# 03_METER_PWM_KEY.net
KiCad netlist of a schematic drawn in Altium Designer
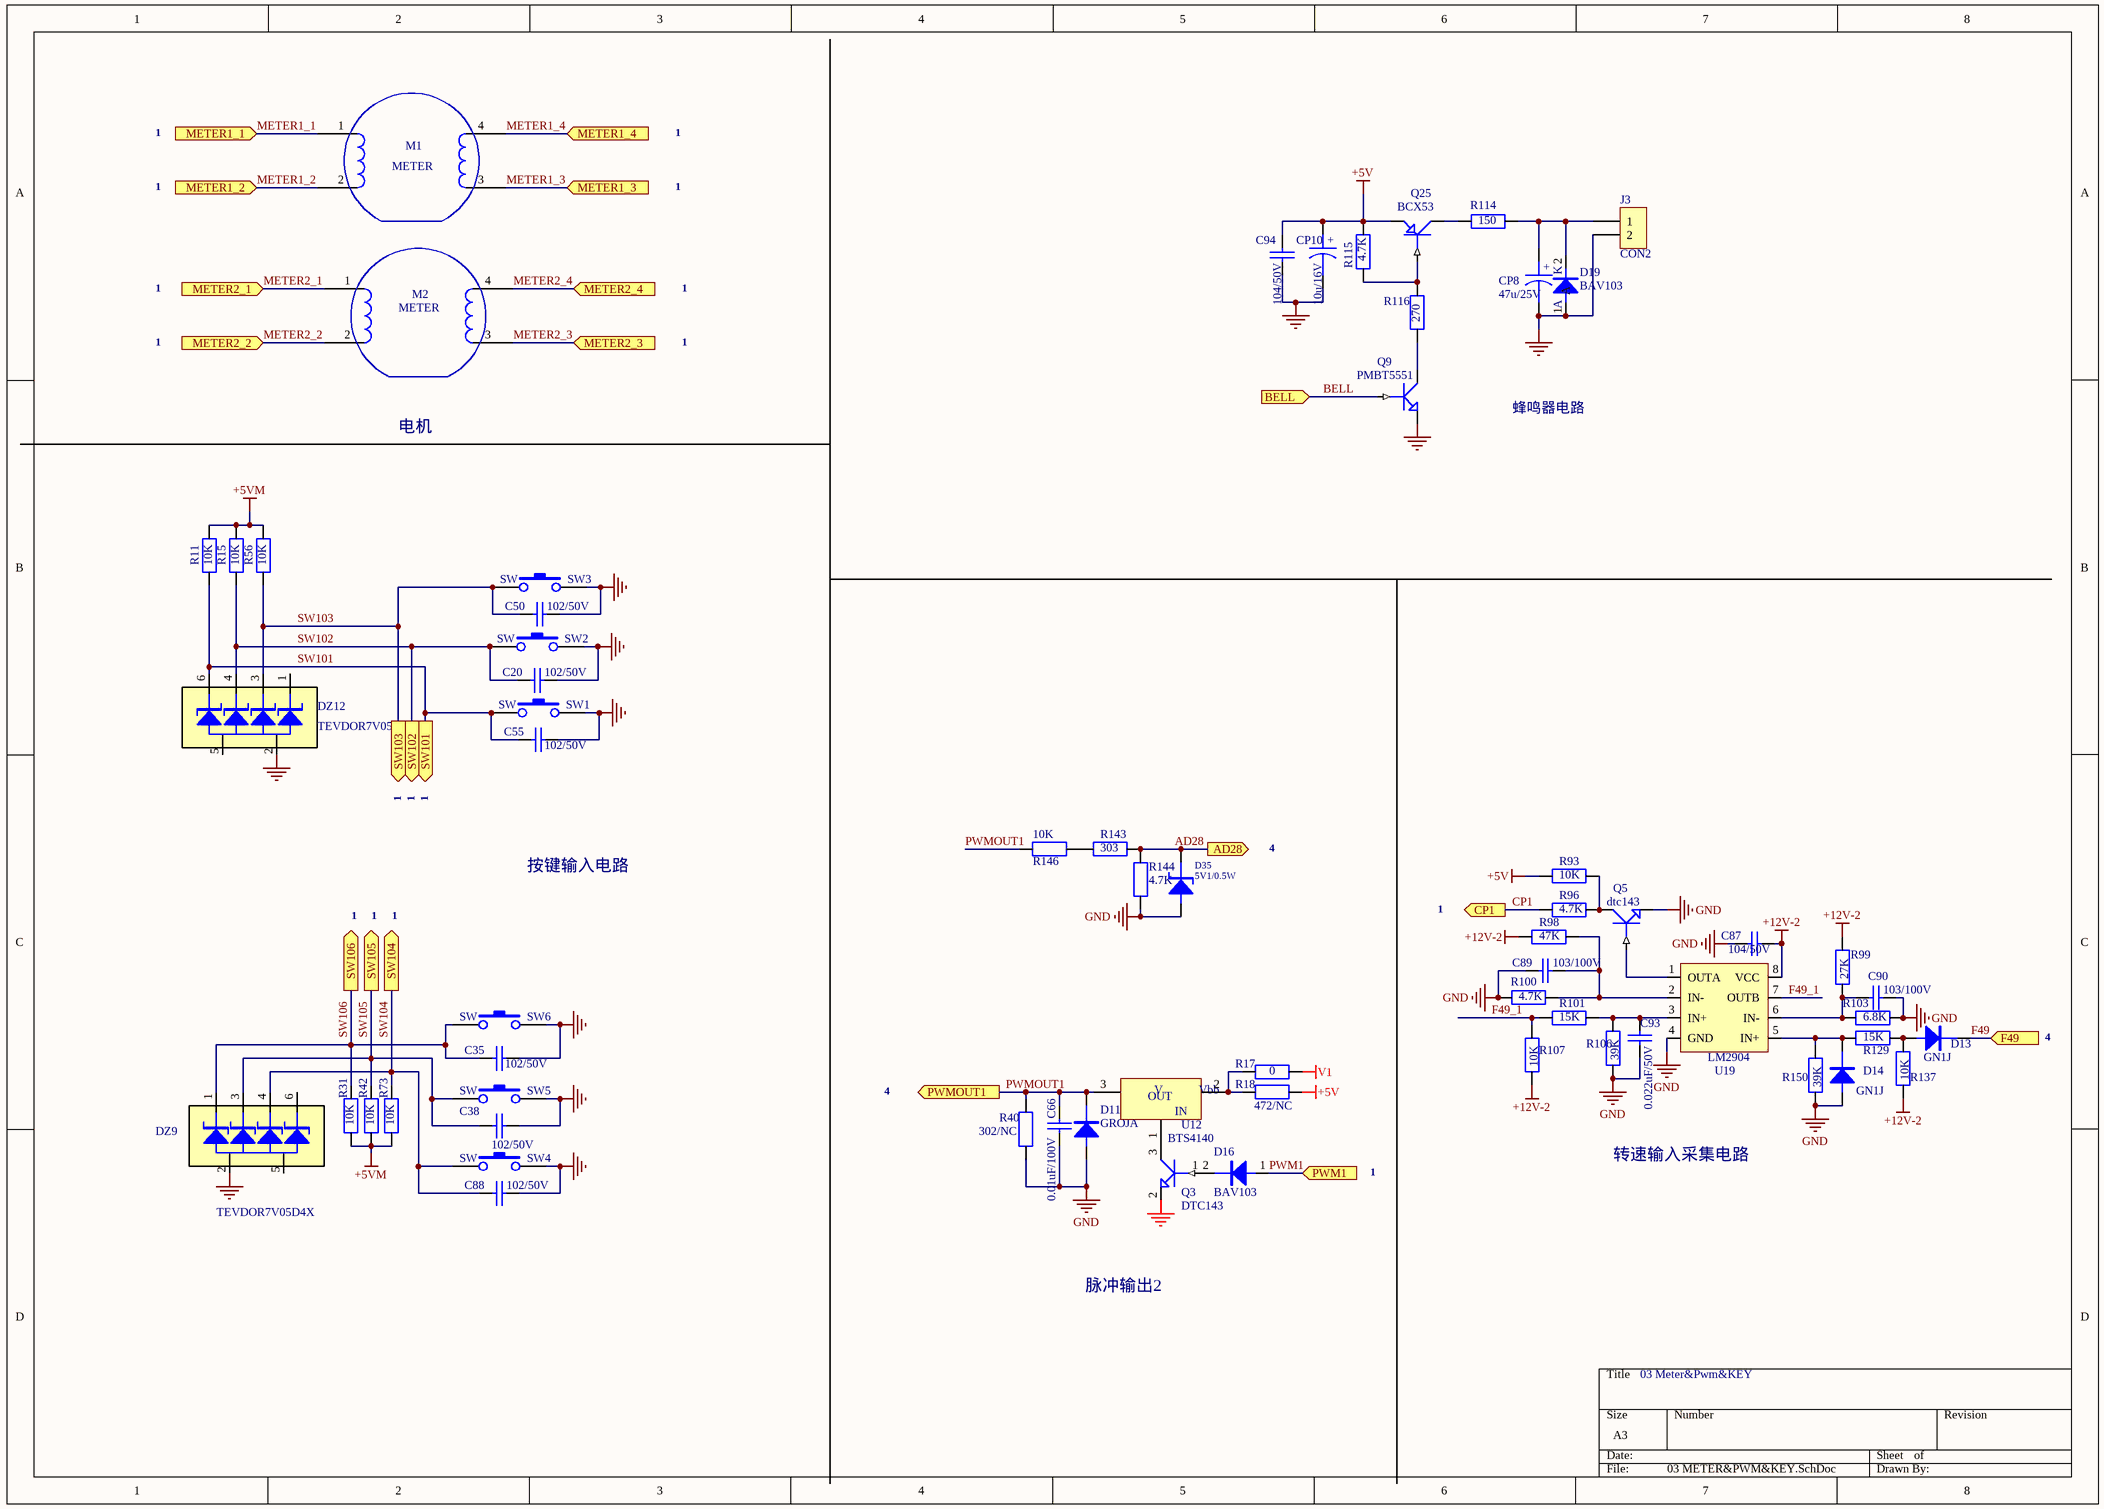
[diagram p0: 03 METER&PWM&KEY.SchDoc]

(export (version "E")
  (design (tool "Eeschema 10.0.6"))
  (components
    (comp (ref "C20")
      (value "102/50V")
      (footprint "CR0805")
      (description "Capacitor")
      (libsource (lib "*") (part "CAP"))
    )
    (comp (ref "C35")
      (value "102/50V")
      (footprint "CR0805")
      (description "Capacitor")
      (libsource (lib "*") (part "CAP"))
    )
    (comp (ref "C38")
      (value "102/50V")
      (footprint "CR0805")
      (description "Capacitor")
      (libsource (lib "*") (part "CAP"))
    )
    (comp (ref "C50")
      (value "102/50V")
      (footprint "CR0805")
      (description "Capacitor")
      (libsource (lib "*") (part "CAP"))
    )
    (comp (ref "C55")
      (value "102/50V")
      (footprint "CR0805")
      (description "Capacitor")
      (libsource (lib "*") (part "CAP"))
    )
    (comp (ref "C66")
      (value "0.01uF/100V")
      (footprint "CR0805")
      (description "Capacitor")
      (libsource (lib "*") (part "CAP"))
    )
    (comp (ref "C87")
      (value "104/50V")
      (footprint "CR0805")
      (description "贴片电容")
      (libsource (lib "HNS-SCH") (part "CAP"))
    )
    (comp (ref "C88")
      (value "102/50V")
      (footprint "CR0805")
      (description "Capacitor")
      (libsource (lib "*") (part "CAP"))
    )
    (comp (ref "C89")
      (value "103/100V")
      (footprint "CR0805")
      (description "贴片电容")
      (libsource (lib "HNS-SCH") (part "CAP"))
    )
    (comp (ref "C90")
      (value "103/100V")
      (footprint "CR0805")
      (description "贴片电容")
      (libsource (lib "HNS-SCH") (part "CAP"))
    )
    (comp (ref "C93")
      (value "0.022uF/50V")
      (footprint "CR0805")
      (description "Capacitor")
      (libsource (lib "*") (part "CAP"))
    )
    (comp (ref "C94")
      (value "104/50V")
      (footprint "CR0805")
      (description "贴片电容")
      (libsource (lib "YDM-SQ-1SCH") (part "CAP"))
    )
    (comp (ref "CP8")
      (value "47u/25V")
      (footprint "10uF/25V")
      (description "Capacitor")
      (libsource (lib "*") (part "CAPACITOR POL"))
    )
    (comp (ref "CP10")
      (value "10u/16V")
      (footprint "CE1206")
      (description "Capacitor")
      (libsource (lib "*") (part "CAPACITOR POL"))
    )
    (comp (ref "D11")
      (value "GROJA")
      (footprint "SMA")
      (description "二极管")
      (libsource (lib "*") (part "DIODE"))
    )
    (comp (ref "D13")
      (value "GN1J")
      (footprint "SMA")
      (description "二极管")
      (libsource (lib "*") (part "DIODE"))
    )
    (comp (ref "D14")
      (value "GN1J")
      (footprint "SMA")
      (description "二极管")
      (libsource (lib "*") (part "DIODE"))
    )
    (comp (ref "D16")
      (value "BAV103")
      (footprint "SOD-80C")
      (description "二极管")
      (libsource (lib "") (part "DIODE_1"))
    )
    (comp (ref "D19")
      (value "BAV103")
      (footprint "SOD-80C")
      (description "二极管")
      (libsource (lib "HNS-SCH") (part "GN1J"))
    )
    (comp (ref "D35")
      (value "5V1/0.5W")
      (footprint "SOD-80C")
      (description "稳压二极管")
      (libsource (lib "*") (part "DW"))
    )
    (comp (ref "DZ9")
      (value "TEVDOR7V05D4X")
      (footprint "SOT-457")
      (description "二极管排")
      (libsource (lib "*") (part "TEVDOR7V05D4X"))
    )
    (comp (ref "DZ12")
      (value "TEVDOR7V05D4X")
      (footprint "SOT-457")
      (description "二极管排")
      (libsource (lib "") (part "TEVDOR7V05D4X_1"))
    )
    (comp (ref "J3")
      (value "CON2")
      (footprint "DIP 1X2 2.5mm")
      (description "连接器-2PIN")
      (libsource (lib "HNS-SCH") (part "CON2"))
    )
    (comp (ref "M1") (value "METER") (footprint "METER2") (libsource (lib "*") (part "METER")))
    (comp (ref "M2") (value "METER") (footprint "METER2") (libsource (lib "*") (part "METER")))
    (comp (ref "Q3")
      (value "DTC143")
      (footprint "SOT23")
      (description "NPN")
      (libsource (lib "") (part "DTC143_1"))
    )
    (comp (ref "Q5")
      (value "dtc143")
      (footprint "SOT-23")
      (description "贴片三极管")
      (libsource (lib "*") (part "NPN1"))
    )
    (comp (ref "Q9")
      (value "PMBT5551")
      (footprint "SMT3")
      (description "NPN")
      (libsource (lib "Ô­ÀíÍ¼¿â-1SCH") (part "DTC143"))
    )
    (comp (ref "Q25")
      (value "BCX53")
      (footprint "SOT89")
      (description "贴片三极管")
      (libsource (lib "*") (part "PNP1"))
    )
    (comp (ref "R11")
      (value "10K")
      (footprint "CR0805")
      (description "贴片电阻")
      (libsource (lib "*") (part "RES"))
    )
    (comp (ref "R15")
      (value "10K")
      (footprint "CR0805")
      (description "贴片电阻")
      (libsource (lib "*") (part "RES"))
    )
    (comp (ref "R17")
      (value "0")
      (footprint "CR1206")
      (description "贴片电阻")
      (libsource (lib "*") (part "RES"))
    )
    (comp (ref "R18")
      (value "472/NC")
      (footprint "CR1206")
      (description "贴片电阻")
      (libsource (lib "*") (part "RES"))
    )
    (comp (ref "R31")
      (value "10K")
      (footprint "CR0805")
      (description "贴片电阻")
      (libsource (lib "YDM-SQ-1SCH") (part "RES"))
    )
    (comp (ref "R40")
      (value "302/NC")
      (footprint "CR0805")
      (description "贴片电阻")
      (libsource (lib "*") (part "RES"))
    )
    (comp (ref "R42")
      (value "10K")
      (footprint "CR0805")
      (description "贴片电阻")
      (libsource (lib "YDM-SQ-1SCH") (part "RES"))
    )
    (comp (ref "R56")
      (value "10K")
      (footprint "CR0805")
      (description "贴片电阻")
      (libsource (lib "*") (part "RES"))
    )
    (comp (ref "R73")
      (value "10K")
      (footprint "CR0805")
      (description "贴片电阻")
      (libsource (lib "*") (part "RES"))
    )
    (comp (ref "R93")
      (value "10K")
      (footprint "CR0805")
      (description "贴片电阻")
      (libsource (lib "*") (part "RES"))
    )
    (comp (ref "R96")
      (value "4.7K")
      (footprint "CR0805")
      (description "贴片电阻")
      (libsource (lib "*") (part "RES"))
    )
    (comp (ref "R98")
      (value "47K")
      (footprint "CR0805")
      (description "贴片电阻")
      (libsource (lib "*") (part "RES"))
    )
    (comp (ref "R99")
      (value "27K")
      (footprint "CR0805")
      (description "贴片电阻")
      (libsource (lib "*") (part "RES"))
    )
    (comp (ref "R100")
      (value "4.7K")
      (footprint "CR0805")
      (description "贴片电阻")
      (libsource (lib "*") (part "RES"))
    )
    (comp (ref "R101")
      (value "15K")
      (footprint "CR0805")
      (description "贴片电阻")
      (libsource (lib "*") (part "RES"))
    )
    (comp (ref "R103")
      (value "6.8K")
      (footprint "CR0805")
      (description "贴片电阻")
      (libsource (lib "*") (part "RES"))
    )
    (comp (ref "R106")
      (value "39K")
      (footprint "CR0805")
      (description "贴片电阻")
      (libsource (lib "*") (part "RES"))
    )
    (comp (ref "R107")
      (value "10K")
      (footprint "CR0805")
      (description "贴片电阻")
      (libsource (lib "*") (part "RES"))
    )
    (comp (ref "R114")
      (value "150")
      (footprint "CR0805")
      (description "贴片电阻")
      (libsource (lib "YDM-SQ-1SCH") (part "RES"))
    )
    (comp (ref "R115")
      (value "4.7K")
      (footprint "CR0805")
      (description "贴片电阻")
      (libsource (lib "YDM-SQ-1SCH") (part "RES"))
    )
    (comp (ref "R116")
      (value "270")
      (footprint "CR0805")
      (description "贴片电阻")
      (libsource (lib "YDM-SQ-1SCH") (part "RES"))
    )
    (comp (ref "R129")
      (value "15K")
      (footprint "CR0805")
      (description "贴片电阻")
      (libsource (lib "*") (part "RES"))
    )
    (comp (ref "R137")
      (value "10K")
      (footprint "CR0805")
      (description "贴片电阻")
      (libsource (lib "*") (part "RES"))
    )
    (comp (ref "R143")
      (value "303")
      (footprint "CR0805")
      (description "贴片电阻")
      (libsource (lib "*") (part "RES"))
    )
    (comp (ref "R144")
      (value "4.7K")
      (footprint "CR0805")
      (description "贴片电阻")
      (libsource (lib "*") (part "RES"))
    )
    (comp (ref "R146")
      (value "10K")
      (footprint "CR1206")
      (description "贴片电阻")
      (libsource (lib "*") (part "RES"))
    )
    (comp (ref "R150")
      (value "39K")
      (footprint "CR0805")
      (description "贴片电阻")
      (libsource (lib "*") (part "RES"))
    )
    (comp (ref "SW1") (value "SW") (footprint "Switch-1") (libsource (lib "*") (part "SW-PB")))
    (comp (ref "SW2") (value "SW") (footprint "Switch-1") (libsource (lib "*") (part "SW-PB")))
    (comp (ref "SW3") (value "SW") (footprint "Switch-1") (libsource (lib "*") (part "SW-PB")))
    (comp (ref "SW4") (value "SW") (footprint "Switch-1") (libsource (lib "*") (part "SW-PB")))
    (comp (ref "SW5") (value "SW") (footprint "Switch-1") (libsource (lib "*") (part "SW-PB")))
    (comp (ref "SW6") (value "SW") (footprint "Switch-1") (libsource (lib "*") (part "SW-PB")))
    (comp (ref "U12")
      (value "BTS4140")
      (footprint "SOT-223")
      (description "IC-单通道功率开关")
      (libsource (lib "Ô­ÀíÍ¼¿â-1SCH") (part "BTS4140"))
    )
    (comp (ref "U19")
      (value "LM2904")
      (footprint "SO-8")
      (description "IC-双路运放")
      (libsource (lib "HNS-SCH") (part "LM2904"))
    )
  )
  (nets
    (net (code "1") (name "+5V") (class "Default")
      (node (ref "C94") (pin "2") (pinfunction "2_2") (pintype "passive"))
      (node (ref "CP10") (pin "1") (pinfunction "1_1") (pintype "passive"))
      (node (ref "Q25") (pin "3") (pinfunction "E_3") (pintype "passive"))
      (node (ref "R115") (pin "1") (pinfunction "1_1") (pintype "passive"))
      (node (ref "R18") (pin "2") (pinfunction "2_2") (pintype "passive"))
      (node (ref "R93") (pin "2") (pinfunction "2_2") (pintype "passive"))
    )
    (net (code "2") (name "+5VM") (class "Default")
      (node (ref "R11") (pin "1") (pinfunction "1_1") (pintype "passive"))
      (node (ref "R15") (pin "1") (pinfunction "1_1") (pintype "passive"))
      (node (ref "R31") (pin "2") (pinfunction "2_2") (pintype "passive"))
      (node (ref "R42") (pin "2") (pinfunction "2_2") (pintype "passive"))
      (node (ref "R56") (pin "1") (pinfunction "1_1") (pintype "passive"))
      (node (ref "R73") (pin "2") (pinfunction "2_2") (pintype "passive"))
    )
    (net (code "3") (name "+12V-2") (class "Default")
      (node (ref "C87") (pin "2") (pinfunction "2_2") (pintype "passive"))
      (node (ref "R107") (pin "1") (pinfunction "1_1") (pintype "passive"))
      (node (ref "R137") (pin "1") (pinfunction "1_1") (pintype "passive"))
      (node (ref "R98") (pin "1") (pinfunction "1_1") (pintype "passive"))
      (node (ref "R99") (pin "2") (pinfunction "2_2") (pintype "passive"))
      (node (ref "U19") (pin "8") (pinfunction "VCC_8") (pintype "passive"))
    )
    (net (code "4") (name "/AD28") (class "Default")
      (node (ref "D35") (pin "1") (pinfunction "A_1") (pintype "passive"))
      (node (ref "R143") (pin "2") (pinfunction "2_2") (pintype "passive"))
      (node (ref "R144") (pin "2") (pinfunction "2_2") (pintype "passive"))
    )
    (net (code "5") (name "/BELL") (class "Default")
      (node (ref "Q9") (pin "2") (pinfunction "B_2") (pintype "input"))
    )
    (net (code "6") (name "/CP1") (class "Default")
      (node (ref "R96") (pin "2") (pinfunction "2_2") (pintype "passive"))
    )
    (net (code "7") (name "/F49") (class "Default")
      (node (ref "D13") (pin "2") (pinfunction "K_2") (pintype "passive"))
    )
    (net (code "8") (name "/F49_1") (class "Default")
      (node (ref "R101") (pin "1") (pinfunction "1_1") (pintype "passive"))
      (node (ref "R107") (pin "2") (pinfunction "2_2") (pintype "passive"))
      (node (ref "U19") (pin "7") (pinfunction "OUTB_7") (pintype "passive"))
    )
    (net (code "9") (name "/METER1_1") (class "Default")
      (node (ref "M1") (pin "1") (pinfunction "1_1") (pintype "passive"))
    )
    (net (code "10") (name "/METER1_2") (class "Default")
      (node (ref "M1") (pin "2") (pinfunction "2_2") (pintype "passive"))
    )
    (net (code "11") (name "/METER1_3") (class "Default")
      (node (ref "M1") (pin "3") (pinfunction "3_3") (pintype "passive"))
    )
    (net (code "12") (name "/METER1_4") (class "Default")
      (node (ref "M1") (pin "4") (pinfunction "4_4") (pintype "passive"))
    )
    (net (code "13") (name "/METER2_1") (class "Default")
      (node (ref "M2") (pin "1") (pinfunction "1_1") (pintype "passive"))
    )
    (net (code "14") (name "/METER2_2") (class "Default")
      (node (ref "M2") (pin "2") (pinfunction "2_2") (pintype "passive"))
    )
    (net (code "15") (name "/METER2_3") (class "Default")
      (node (ref "M2") (pin "3") (pinfunction "3_3") (pintype "passive"))
    )
    (net (code "16") (name "/METER2_4") (class "Default")
      (node (ref "M2") (pin "4") (pinfunction "4_4") (pintype "passive"))
    )
    (net (code "17") (name "/PWM1") (class "Default")
      (node (ref "D16") (pin "1") (pinfunction "A_1") (pintype "passive"))
    )
    (net (code "18") (name "/PWMOUT1") (class "Default")
      (node (ref "C66") (pin "1") (pinfunction "1_1") (pintype "passive"))
      (node (ref "D11") (pin "2") (pinfunction "K_2") (pintype "passive"))
      (node (ref "R146") (pin "1") (pinfunction "1_1") (pintype "passive"))
      (node (ref "R40") (pin "2") (pinfunction "2_2") (pintype "passive"))
      (node (ref "U12") (pin "3") (pinfunction "VOUT_3") (pintype "passive"))
    )
    (net (code "19") (name "/SW101") (class "Default")
      (node (ref "C55") (pin "2") (pinfunction "2_2") (pintype "passive"))
      (node (ref "DZ12") (pin "6") (pintype "passive"))
      (node (ref "R11") (pin "2") (pinfunction "2_2") (pintype "passive"))
      (node (ref "SW1") (pin "1") (pinfunction "1_1") (pintype "passive"))
    )
    (net (code "20") (name "/SW102") (class "Default")
      (node (ref "C20") (pin "2") (pinfunction "2_2") (pintype "passive"))
      (node (ref "DZ12") (pin "4") (pintype "passive"))
      (node (ref "R15") (pin "2") (pinfunction "2_2") (pintype "passive"))
      (node (ref "SW2") (pin "1") (pinfunction "1_1") (pintype "passive"))
    )
    (net (code "21") (name "/SW103") (class "Default")
      (node (ref "C50") (pin "2") (pinfunction "2_2") (pintype "passive"))
      (node (ref "DZ12") (pin "3") (pintype "passive"))
      (node (ref "R56") (pin "2") (pinfunction "2_2") (pintype "passive"))
      (node (ref "SW3") (pin "1") (pinfunction "1_1") (pintype "passive"))
    )
    (net (code "22") (name "/SW104") (class "Default")
      (node (ref "C88") (pin "2") (pinfunction "2_2") (pintype "passive"))
      (node (ref "DZ9") (pin "4") (pintype "passive"))
      (node (ref "R73") (pin "1") (pinfunction "1_1") (pintype "passive"))
      (node (ref "SW4") (pin "1") (pinfunction "1_1") (pintype "passive"))
    )
    (net (code "23") (name "/SW105") (class "Default")
      (node (ref "C38") (pin "1") (pinfunction "1_1") (pintype "passive"))
      (node (ref "DZ9") (pin "3") (pintype "passive"))
      (node (ref "R42") (pin "1") (pinfunction "1_1") (pintype "passive"))
      (node (ref "SW5") (pin "1") (pinfunction "1_1") (pintype "passive"))
    )
    (net (code "24") (name "/SW106") (class "Default")
      (node (ref "C35") (pin "2") (pinfunction "2_2") (pintype "passive"))
      (node (ref "DZ9") (pin "1") (pintype "passive"))
      (node (ref "R31") (pin "1") (pinfunction "1_1") (pintype "passive"))
      (node (ref "SW6") (pin "1") (pinfunction "1_1") (pintype "passive"))
    )
    (net (code "25") (name "GND") (class "Default")
      (node (ref "C20") (pin "1") (pinfunction "1_1") (pintype "passive"))
      (node (ref "C35") (pin "1") (pinfunction "1_1") (pintype "passive"))
      (node (ref "C38") (pin "2") (pinfunction "2_2") (pintype "passive"))
      (node (ref "C50") (pin "1") (pinfunction "1_1") (pintype "passive"))
      (node (ref "C55") (pin "1") (pinfunction "1_1") (pintype "passive"))
      (node (ref "C66") (pin "2") (pinfunction "2_2") (pintype "passive"))
      (node (ref "C87") (pin "1") (pinfunction "1_1") (pintype "passive"))
      (node (ref "C88") (pin "1") (pinfunction "1_1") (pintype "passive"))
      (node (ref "C89") (pin "2") (pinfunction "2_2") (pintype "passive"))
      (node (ref "C90") (pin "2") (pinfunction "2_2") (pintype "passive"))
      (node (ref "C93") (pin "1") (pinfunction "1_1") (pintype "passive"))
      (node (ref "C94") (pin "1") (pinfunction "1_1") (pintype "passive"))
      (node (ref "CP10") (pin "2") (pinfunction "2_2") (pintype "passive"))
      (node (ref "CP8") (pin "2") (pinfunction "2_2") (pintype "passive"))
      (node (ref "D11") (pin "1") (pinfunction "A_1") (pintype "passive"))
      (node (ref "D14") (pin "1") (pinfunction "A_1") (pintype "passive"))
      (node (ref "D19") (pin "1") (pinfunction "A_1") (pintype "passive"))
      (node (ref "D35") (pin "2") (pinfunction "K_2") (pintype "passive"))
      (node (ref "DZ12") (pin "2") (pintype "passive"))
      (node (ref "DZ9") (pin "2") (pintype "passive"))
      (node (ref "J3") (pin "2") (pinfunction "2_2") (pintype "passive"))
      (node (ref "Q3") (pin "2") (pinfunction "gnd_2") (pintype "passive"))
      (node (ref "Q5") (pin "3") (pinfunction "E_3") (pintype "passive"))
      (node (ref "Q9") (pin "1") (pinfunction "E_1") (pintype "passive"))
      (node (ref "R100") (pin "2") (pinfunction "2_2") (pintype "passive"))
      (node (ref "R103") (pin "2") (pinfunction "2_2") (pintype "passive"))
      (node (ref "R106") (pin "1") (pinfunction "1_1") (pintype "passive"))
      (node (ref "R144") (pin "1") (pinfunction "1_1") (pintype "passive"))
      (node (ref "R150") (pin "1") (pinfunction "1_1") (pintype "passive"))
      (node (ref "R40") (pin "1") (pinfunction "1_1") (pintype "passive"))
      (node (ref "SW1") (pin "2") (pinfunction "2_2") (pintype "passive"))
      (node (ref "SW2") (pin "2") (pinfunction "2_2") (pintype "passive"))
      (node (ref "SW3") (pin "2") (pinfunction "2_2") (pintype "passive"))
      (node (ref "SW4") (pin "2") (pinfunction "2_2") (pintype "passive"))
      (node (ref "SW5") (pin "2") (pinfunction "2_2") (pintype "passive"))
      (node (ref "SW6") (pin "2") (pinfunction "2_2") (pintype "passive"))
      (node (ref "U19") (pin "4") (pinfunction "GND_4") (pintype "passive"))
    )
    (net (code "26") (name "Net-(C89-Pad1)") (class "Default")
      (node (ref "C89") (pin "1") (pinfunction "1_1") (pintype "passive"))
      (node (ref "R100") (pin "1") (pinfunction "1_1") (pintype "passive"))
      (node (ref "R98") (pin "2") (pinfunction "2_2") (pintype "passive"))
      (node (ref "U19") (pin "2") (pinfunction "IN-_2") (pintype "passive"))
    )
    (net (code "27") (name "Net-(C90-Pad1)") (class "Default")
      (node (ref "C90") (pin "1") (pinfunction "1_1") (pintype "passive"))
      (node (ref "R103") (pin "1") (pinfunction "1_1") (pintype "passive"))
      (node (ref "R99") (pin "1") (pinfunction "1_1") (pintype "passive"))
      (node (ref "U19") (pin "6") (pinfunction "IN-_6") (pintype "passive"))
    )
    (net (code "28") (name "Net-(C93-Pad2)") (class "Default")
      (node (ref "C93") (pin "2") (pinfunction "2_2") (pintype "passive"))
      (node (ref "R101") (pin "2") (pinfunction "2_2") (pintype "passive"))
      (node (ref "R106") (pin "2") (pinfunction "2_2") (pintype "passive"))
      (node (ref "U19") (pin "3") (pinfunction "IN+_3") (pintype "passive"))
    )
    (net (code "29") (name "Net-(D13-A)") (class "Default")
      (node (ref "D13") (pin "1") (pinfunction "A_1") (pintype "passive"))
      (node (ref "R129") (pin "2") (pinfunction "2_2") (pintype "passive"))
      (node (ref "R137") (pin "2") (pinfunction "2_2") (pintype "passive"))
    )
    (net (code "30") (name "Net-(D14-K)") (class "Default")
      (node (ref "D14") (pin "2") (pinfunction "K_2") (pintype "passive"))
      (node (ref "R129") (pin "1") (pinfunction "1_1") (pintype "passive"))
      (node (ref "R150") (pin "2") (pinfunction "2_2") (pintype "passive"))
      (node (ref "U19") (pin "5") (pinfunction "IN+_5") (pintype "passive"))
    )
    (net (code "31") (name "Net-(D16-K)") (class "Default")
      (node (ref "D16") (pin "2") (pinfunction "K_2") (pintype "passive"))
      (node (ref "Q3") (pin "1") (pinfunction "in_1") (pintype "input"))
    )
    (net (code "32") (name "Net-(D19-K)") (class "Default")
      (node (ref "CP8") (pin "1") (pinfunction "1_1") (pintype "passive"))
      (node (ref "D19") (pin "2") (pinfunction "K_2") (pintype "passive"))
      (node (ref "J3") (pin "1") (pinfunction "1_1") (pintype "passive"))
      (node (ref "R114") (pin "1") (pinfunction "1_1") (pintype "passive"))
    )
    (net (code "33") (name "Net-(Q3-out)") (class "Default")
      (node (ref "Q3") (pin "3") (pinfunction "out_3") (pintype "passive"))
      (node (ref "U12") (pin "1") (pinfunction "IN_1") (pintype "passive"))
    )
    (net (code "34") (name "Net-(Q5-B)") (class "Default")
      (node (ref "Q5") (pin "1") (pinfunction "B_1") (pintype "input"))
      (node (ref "U19") (pin "1") (pinfunction "OUTA_1") (pintype "passive"))
    )
    (net (code "35") (name "Net-(Q5-C)") (class "Default")
      (node (ref "Q5") (pin "2") (pinfunction "C_2") (pintype "passive"))
      (node (ref "R93") (pin "1") (pinfunction "1_1") (pintype "passive"))
      (node (ref "R96") (pin "1") (pinfunction "1_1") (pintype "passive"))
    )
    (net (code "36") (name "Net-(Q9-C)") (class "Default")
      (node (ref "Q9") (pin "3") (pinfunction "C_3") (pintype "passive"))
      (node (ref "R116") (pin "1") (pinfunction "1_1") (pintype "passive"))
    )
    (net (code "37") (name "Net-(Q25-B)") (class "Default")
      (node (ref "Q25") (pin "1") (pinfunction "B_1") (pintype "input"))
      (node (ref "R115") (pin "2") (pinfunction "2_2") (pintype "passive"))
      (node (ref "R116") (pin "2") (pinfunction "2_2") (pintype "passive"))
    )
    (net (code "38") (name "Net-(Q25-C)") (class "Default")
      (node (ref "Q25") (pin "2") (pinfunction "C_2") (pintype "passive"))
      (node (ref "R114") (pin "2") (pinfunction "2_2") (pintype "passive"))
    )
    (net (code "39") (name "Net-(R17-Pad1)") (class "Default")
      (node (ref "R17") (pin "1") (pinfunction "1_1") (pintype "passive"))
      (node (ref "R18") (pin "1") (pinfunction "1_1") (pintype "passive"))
      (node (ref "U12") (pin "2") (pinfunction "Vbb_2") (pintype "passive"))
      (node (ref "U12") (pin "4") (pinfunction "Vbb_4") (pintype "passive"))
    )
    (net (code "40") (name "Net-(R143-Pad1)") (class "Default")
      (node (ref "R143") (pin "1") (pinfunction "1_1") (pintype "passive"))
      (node (ref "R146") (pin "2") (pinfunction "2_2") (pintype "passive"))
    )
    (net (code "41") (name "V1") (class "Default")
      (node (ref "R17") (pin "2") (pinfunction "2_2") (pintype "passive"))
    )
    (net (code "42") (name "unconnected-(DZ9-Pad5)") (class "Default")
      (node (ref "DZ9") (pin "5") (pintype "passive"))
    )
    (net (code "43") (name "unconnected-(DZ9-Pad6)") (class "Default")
      (node (ref "DZ9") (pin "6") (pintype "passive"))
    )
    (net (code "44") (name "unconnected-(DZ12-Pad1)") (class "Default")
      (node (ref "DZ12") (pin "1") (pintype "passive"))
    )
    (net (code "45") (name "unconnected-(DZ12-Pad5)") (class "Default")
      (node (ref "DZ12") (pin "5") (pintype "passive"))
    )
  )
)
